# WiirdFlex_Bottom_Alignment.net
KiCad netlist of a schematic drawn in Altium Designer
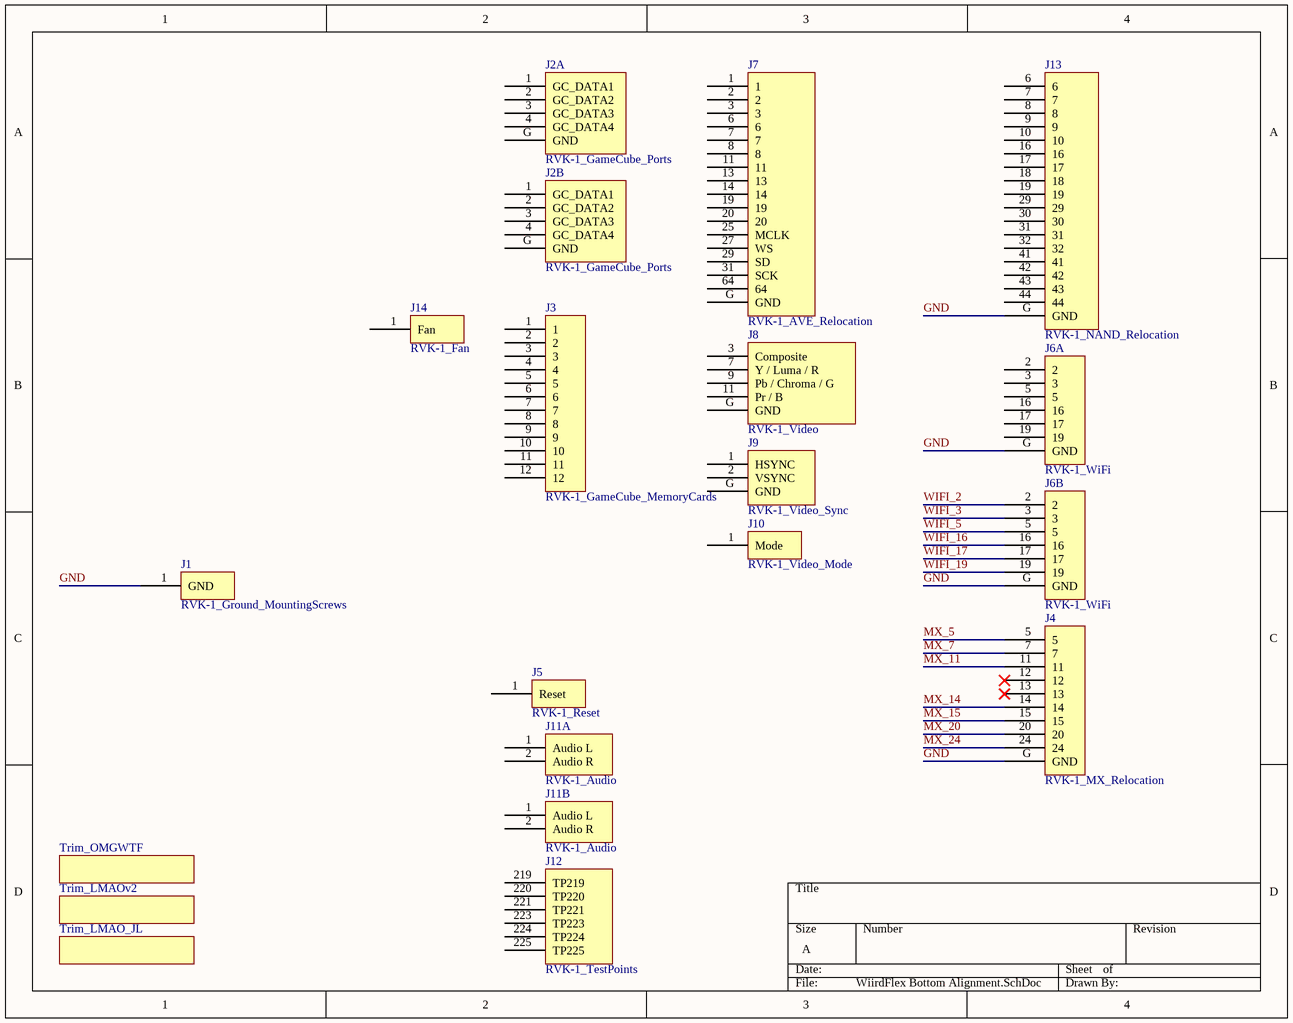
[diagram p0: WiirdFlex Bottom Alignment.SchDoc]

(export (version "E")
  (design (tool "Eeschema 10.0.6"))
  (components
    (comp (ref "J1")
      (value "RVK-1_Ground_MountingScrews")
      (footprint "RVK-1_GND_Screws - bottom alignment board")
      (libsource (lib "WiirdFlex") (part "RVK-1_Ground_MountingScrews"))
    )
    (comp (ref "J2A")
      (value "RVK-1_GameCube_Ports")
      (footprint "RVK-1_GC_Controller_RPads - alignment")
      (libsource (lib "WiirdFlex") (part "RVK-1_GameCube_Ports"))
    )
    (comp (ref "J2B")
      (value "RVK-1_GameCube_Ports")
      (footprint "RVK-1_GC_Controller_Vias - alignment")
      (libsource (lib "WiirdFlex") (part "RVK-1_GameCube_Ports"))
    )
    (comp (ref "J3")
      (value "RVK-1_GameCube_MemoryCards")
      (footprint "RVK-1_MemCard_TestPoints - alignment")
      (libsource (lib "WiirdFlex") (part "RVK-1_GameCube_MemoryCards"))
    )
    (comp (ref "J4")
      (value "RVK-1_MX_Relocation")
      (footprint "RVK-1_MX - alignment")
      (libsource (lib "WiirdFlex") (part "RVK-1_MX_Relocation"))
    )
    (comp (ref "J5")
      (value "RVK-1_Reset")
      (footprint "RVK-1_Reset - alignment")
      (libsource (lib "WiirdFlex") (part "RVK-1_Reset"))
    )
    (comp (ref "J6A")
      (value "RVK-1_WiFi")
      (footprint "RVK-1_WiFi_RPads - Alignment")
      (libsource (lib "WiirdFlex") (part "RVK-1_WiFi"))
    )
    (comp (ref "J6B")
      (value "RVK-1_WiFi")
      (footprint "RVK-1_WiFi_Vias - Alignment")
      (libsource (lib "WiirdFlex") (part "RVK-1_WiFi"))
    )
    (comp (ref "J7")
      (value "RVK-1_AVE_Relocation")
      (footprint "RVK-1_AVE_Vias - alignment")
      (libsource (lib "WiirdFlex") (part "RVK-1_AVE_Relocation"))
    )
    (comp (ref "J8")
      (value "RVK-1_Video")
      (footprint "RVK-1_Video_Vias - alignment")
      (libsource (lib "WiirdFlex") (part "RVK-1_Video"))
    )
    (comp (ref "J9")
      (value "RVK-1_Video_Sync")
      (footprint "RVK-1_Video_Sync - alignment")
      (libsource (lib "WiirdFlex") (part "RVK-1_Video_Sync"))
    )
    (comp (ref "J10")
      (value "RVK-1_Video_Mode")
      (footprint "RVK-1_Video_Mode_via - alignment")
      (libsource (lib "WiirdFlex") (part "RVK-1_Video_Mode"))
    )
    (comp (ref "J11A")
      (value "RVK-1_Audio")
      (footprint "RVK-1_AVE_Audio_Out - alignment")
      (libsource (lib "WiirdFlex") (part "RVK-1_Audio"))
    )
    (comp (ref "J11B")
      (value "RVK-1_Audio")
      (footprint "RVK-1_Audio_Preamp_Pads - alignment")
      (libsource (lib "WiirdFlex") (part "RVK-1_Audio"))
    )
    (comp (ref "J12")
      (value "RVK-1_TestPoints")
      (footprint "RVK-1_TestPoint_Vias - alignment")
      (libsource (lib "WiirdFlex") (part "RVK-1_TestPoints"))
    )
    (comp (ref "J13")
      (value "RVK-1_NAND_Relocation")
      (footprint "RVK-1_NAND_Vias - alignment")
      (libsource (lib "WiirdFlex") (part "RVK-1_NAND_Relocation"))
    )
    (comp (ref "J14")
      (value "RVK-1_Fan")
      (footprint "RVK-1_Fan_PWM - alignment")
      (libsource (lib "WiirdFlex") (part "RVK-1_Fan"))
    )
    (comp (ref "Trim_LMAOv2")
      (value "Misc")
      (footprint "Wii trim: LMAOv2")
      (description "placeholder for footprints without pads - keepouts, trim outlines, etc")
      (libsource (lib "WiirdFlex") (part "Misc"))
    )
    (comp (ref "Trim_LMAO_JL")
      (value "Misc")
      (footprint "Wii Trim: LMAO with extra mounting hole")
      (description "placeholder for footprints without pads - keepouts, trim outlines, etc")
      (libsource (lib "WiirdFlex") (part "Misc"))
    )
    (comp (ref "Trim_OMGWTF")
      (value "Misc")
      (footprint "Wii trim: OMGWTF")
      (description "placeholder for footprints without pads - keepouts, trim outlines, etc")
      (libsource (lib "WiirdFlex") (part "Misc"))
    )
  )
  (nets
    (net (code "1") (name "/GND") (class "Default")
      (node (ref "J1") (pin "1") (pinfunction "GND_1") (pintype "passive"))
      (node (ref "J13") (pin "G") (pinfunction "GND_G") (pintype "passive"))
      (node (ref "J4") (pin "G") (pinfunction "GND_G") (pintype "passive"))
      (node (ref "J6A") (pin "G") (pinfunction "GND_G") (pintype "passive"))
      (node (ref "J6B") (pin "G") (pinfunction "GND_G") (pintype "passive"))
    )
    (net (code "2") (name "/MX_5") (class "Default")
      (node (ref "J4") (pin "5") (pinfunction "5_5") (pintype "passive"))
    )
    (net (code "3") (name "/MX_7") (class "Default")
      (node (ref "J4") (pin "7") (pinfunction "7_7") (pintype "passive"))
    )
    (net (code "4") (name "/MX_11") (class "Default")
      (node (ref "J4") (pin "11") (pinfunction "11_11") (pintype "passive"))
    )
    (net (code "5") (name "/MX_14") (class "Default")
      (node (ref "J4") (pin "14") (pinfunction "14_14") (pintype "passive"))
    )
    (net (code "6") (name "/MX_15") (class "Default")
      (node (ref "J4") (pin "15") (pinfunction "15_15") (pintype "passive"))
    )
    (net (code "7") (name "/MX_20") (class "Default")
      (node (ref "J4") (pin "20") (pinfunction "20_20") (pintype "passive"))
    )
    (net (code "8") (name "/MX_24") (class "Default")
      (node (ref "J4") (pin "24") (pinfunction "24_24") (pintype "passive"))
    )
    (net (code "9") (name "/WIFI_2") (class "Default")
      (node (ref "J6B") (pin "2") (pinfunction "2_2") (pintype "passive"))
    )
    (net (code "10") (name "/WIFI_3") (class "Default")
      (node (ref "J6B") (pin "3") (pinfunction "3_3") (pintype "passive"))
    )
    (net (code "11") (name "/WIFI_5") (class "Default")
      (node (ref "J6B") (pin "5") (pinfunction "5_5") (pintype "passive"))
    )
    (net (code "12") (name "/WIFI_16") (class "Default")
      (node (ref "J6B") (pin "16") (pinfunction "16_16") (pintype "passive"))
    )
    (net (code "13") (name "/WIFI_17") (class "Default")
      (node (ref "J6B") (pin "17") (pinfunction "17_17") (pintype "passive"))
    )
    (net (code "14") (name "/WIFI_19") (class "Default")
      (node (ref "J6B") (pin "19") (pinfunction "19_19") (pintype "passive"))
    )
    (net (code "15") (name "unconnected-(J2A-GC_DATA1-Pad1)") (class "Default")
      (node (ref "J2A") (pin "1") (pinfunction "GC_DATA1_1") (pintype "passive"))
    )
    (net (code "16") (name "unconnected-(J2A-GC_DATA2-Pad2)") (class "Default")
      (node (ref "J2A") (pin "2") (pinfunction "GC_DATA2_2") (pintype "passive"))
    )
    (net (code "17") (name "unconnected-(J2A-GC_DATA3-Pad3)") (class "Default")
      (node (ref "J2A") (pin "3") (pinfunction "GC_DATA3_3") (pintype "passive"))
    )
    (net (code "18") (name "unconnected-(J2A-GC_DATA4-Pad4)") (class "Default")
      (node (ref "J2A") (pin "4") (pinfunction "GC_DATA4_4") (pintype "passive"))
    )
    (net (code "19") (name "unconnected-(J2A-GND-PadG)") (class "Default")
      (node (ref "J2A") (pin "G") (pinfunction "GND_G") (pintype "passive"))
    )
    (net (code "20") (name "unconnected-(J2B-GC_DATA1-Pad1)") (class "Default")
      (node (ref "J2B") (pin "1") (pinfunction "GC_DATA1_1") (pintype "passive"))
    )
    (net (code "21") (name "unconnected-(J2B-GC_DATA2-Pad2)") (class "Default")
      (node (ref "J2B") (pin "2") (pinfunction "GC_DATA2_2") (pintype "passive"))
    )
    (net (code "22") (name "unconnected-(J2B-GC_DATA3-Pad3)") (class "Default")
      (node (ref "J2B") (pin "3") (pinfunction "GC_DATA3_3") (pintype "passive"))
    )
    (net (code "23") (name "unconnected-(J2B-GC_DATA4-Pad4)") (class "Default")
      (node (ref "J2B") (pin "4") (pinfunction "GC_DATA4_4") (pintype "passive"))
    )
    (net (code "24") (name "unconnected-(J2B-GND-PadG)") (class "Default")
      (node (ref "J2B") (pin "G") (pinfunction "GND_G") (pintype "passive"))
    )
    (net (code "25") (name "unconnected-(J3-Pad1)") (class "Default")
      (node (ref "J3") (pin "1") (pinfunction "1_1") (pintype "passive"))
    )
    (net (code "26") (name "unconnected-(J3-Pad2)") (class "Default")
      (node (ref "J3") (pin "2") (pinfunction "2_2") (pintype "passive"))
    )
    (net (code "27") (name "unconnected-(J3-Pad3)") (class "Default")
      (node (ref "J3") (pin "3") (pinfunction "3_3") (pintype "passive"))
    )
    (net (code "28") (name "unconnected-(J3-Pad4)") (class "Default")
      (node (ref "J3") (pin "4") (pinfunction "4_4") (pintype "passive"))
    )
    (net (code "29") (name "unconnected-(J3-Pad5)") (class "Default")
      (node (ref "J3") (pin "5") (pinfunction "5_5") (pintype "passive"))
    )
    (net (code "30") (name "unconnected-(J3-Pad6)") (class "Default")
      (node (ref "J3") (pin "6") (pinfunction "6_6") (pintype "passive"))
    )
    (net (code "31") (name "unconnected-(J3-Pad7)") (class "Default")
      (node (ref "J3") (pin "7") (pinfunction "7_7") (pintype "passive"))
    )
    (net (code "32") (name "unconnected-(J3-Pad8)") (class "Default")
      (node (ref "J3") (pin "8") (pinfunction "8_8") (pintype "passive"))
    )
    (net (code "33") (name "unconnected-(J3-Pad9)") (class "Default")
      (node (ref "J3") (pin "9") (pinfunction "9_9") (pintype "passive"))
    )
    (net (code "34") (name "unconnected-(J3-Pad10)") (class "Default")
      (node (ref "J3") (pin "10") (pinfunction "10_10") (pintype "passive"))
    )
    (net (code "35") (name "unconnected-(J3-Pad11)") (class "Default")
      (node (ref "J3") (pin "11") (pinfunction "11_11") (pintype "passive"))
    )
    (net (code "36") (name "unconnected-(J3-Pad12)") (class "Default")
      (node (ref "J3") (pin "12") (pinfunction "12_12") (pintype "passive"))
    )
    (net (code "37") (name "unconnected-(J4-Pad12)") (class "Default")
      (node (ref "J4") (pin "12") (pinfunction "12_12") (pintype "passive+no_connect"))
    )
    (net (code "38") (name "unconnected-(J4-Pad13)") (class "Default")
      (node (ref "J4") (pin "13") (pinfunction "13_13") (pintype "passive+no_connect"))
    )
    (net (code "39") (name "unconnected-(J5-Reset-Pad1)") (class "Default")
      (node (ref "J5") (pin "1") (pinfunction "Reset_1") (pintype "passive"))
    )
    (net (code "40") (name "unconnected-(J6A-Pad2)") (class "Default")
      (node (ref "J6A") (pin "2") (pinfunction "2_2") (pintype "passive"))
    )
    (net (code "41") (name "unconnected-(J6A-Pad3)") (class "Default")
      (node (ref "J6A") (pin "3") (pinfunction "3_3") (pintype "passive"))
    )
    (net (code "42") (name "unconnected-(J6A-Pad5)") (class "Default")
      (node (ref "J6A") (pin "5") (pinfunction "5_5") (pintype "passive"))
    )
    (net (code "43") (name "unconnected-(J6A-Pad16)") (class "Default")
      (node (ref "J6A") (pin "16") (pinfunction "16_16") (pintype "passive"))
    )
    (net (code "44") (name "unconnected-(J6A-Pad17)") (class "Default")
      (node (ref "J6A") (pin "17") (pinfunction "17_17") (pintype "passive"))
    )
    (net (code "45") (name "unconnected-(J6A-Pad19)") (class "Default")
      (node (ref "J6A") (pin "19") (pinfunction "19_19") (pintype "passive"))
    )
    (net (code "46") (name "unconnected-(J7-GND-PadG)") (class "Default")
      (node (ref "J7") (pin "G") (pinfunction "GND_G") (pintype "passive"))
    )
    (net (code "47") (name "unconnected-(J7-MCLK-Pad25)") (class "Default")
      (node (ref "J7") (pin "25") (pinfunction "MCLK_25") (pintype "passive"))
    )
    (net (code "48") (name "unconnected-(J7-Pad1)") (class "Default")
      (node (ref "J7") (pin "1") (pinfunction "1_1") (pintype "passive"))
    )
    (net (code "49") (name "unconnected-(J7-Pad2)") (class "Default")
      (node (ref "J7") (pin "2") (pinfunction "2_2") (pintype "passive"))
    )
    (net (code "50") (name "unconnected-(J7-Pad3)") (class "Default")
      (node (ref "J7") (pin "3") (pinfunction "3_3") (pintype "passive"))
    )
    (net (code "51") (name "unconnected-(J7-Pad6)") (class "Default")
      (node (ref "J7") (pin "6") (pinfunction "6_6") (pintype "passive"))
    )
    (net (code "52") (name "unconnected-(J7-Pad7)") (class "Default")
      (node (ref "J7") (pin "7") (pinfunction "7_7") (pintype "passive"))
    )
    (net (code "53") (name "unconnected-(J7-Pad8)") (class "Default")
      (node (ref "J7") (pin "8") (pinfunction "8_8") (pintype "passive"))
    )
    (net (code "54") (name "unconnected-(J7-Pad11)") (class "Default")
      (node (ref "J7") (pin "11") (pinfunction "11_11") (pintype "passive"))
    )
    (net (code "55") (name "unconnected-(J7-Pad13)") (class "Default")
      (node (ref "J7") (pin "13") (pinfunction "13_13") (pintype "passive"))
    )
    (net (code "56") (name "unconnected-(J7-Pad14)") (class "Default")
      (node (ref "J7") (pin "14") (pinfunction "14_14") (pintype "passive"))
    )
    (net (code "57") (name "unconnected-(J7-Pad19)") (class "Default")
      (node (ref "J7") (pin "19") (pinfunction "19_19") (pintype "passive"))
    )
    (net (code "58") (name "unconnected-(J7-Pad20)") (class "Default")
      (node (ref "J7") (pin "20") (pinfunction "20_20") (pintype "passive"))
    )
    (net (code "59") (name "unconnected-(J7-Pad64)") (class "Default")
      (node (ref "J7") (pin "64") (pinfunction "64_64") (pintype "passive"))
    )
    (net (code "60") (name "unconnected-(J7-SCK-Pad31)") (class "Default")
      (node (ref "J7") (pin "31") (pinfunction "SCK_31") (pintype "passive"))
    )
    (net (code "61") (name "unconnected-(J7-SD-Pad29)") (class "Default")
      (node (ref "J7") (pin "29") (pinfunction "SD_29") (pintype "passive"))
    )
    (net (code "62") (name "unconnected-(J7-WS-Pad27)") (class "Default")
      (node (ref "J7") (pin "27") (pinfunction "WS_27") (pintype "passive"))
    )
    (net (code "63") (name "unconnected-(J8-Composite-Pad3)") (class "Default")
      (node (ref "J8") (pin "3") (pinfunction "Composite_3") (pintype "passive"))
    )
    (net (code "64") (name "unconnected-(J8-GND-PadG)") (class "Default")
      (node (ref "J8") (pin "G") (pinfunction "GND_G") (pintype "passive"))
    )
    (net (code "65") (name "unconnected-(J8-Pb_{slash}_Chroma_{slash}_G-Pad9)") (class "Default")
      (node (ref "J8") (pin "9") (pinfunction "Pb_/_Chroma_/_G_9") (pintype "passive"))
    )
    (net (code "66") (name "unconnected-(J8-Pr_{slash}_B-Pad11)") (class "Default")
      (node (ref "J8") (pin "11") (pinfunction "Pr_/_B_11") (pintype "passive"))
    )
    (net (code "67") (name "unconnected-(J8-Y_{slash}_Luma_{slash}_R-Pad7)") (class "Default")
      (node (ref "J8") (pin "7") (pinfunction "Y_/_Luma_/_R_7") (pintype "passive"))
    )
    (net (code "68") (name "unconnected-(J9-GND-PadG)") (class "Default")
      (node (ref "J9") (pin "G") (pinfunction "GND_G") (pintype "passive"))
    )
    (net (code "69") (name "unconnected-(J9-HSYNC-Pad1)") (class "Default")
      (node (ref "J9") (pin "1") (pinfunction "HSYNC_1") (pintype "passive"))
    )
    (net (code "70") (name "unconnected-(J9-VSYNC-Pad2)") (class "Default")
      (node (ref "J9") (pin "2") (pinfunction "VSYNC_2") (pintype "passive"))
    )
    (net (code "71") (name "unconnected-(J10-Mode-Pad1)") (class "Default")
      (node (ref "J10") (pin "1") (pinfunction "Mode_1") (pintype "passive"))
    )
    (net (code "72") (name "unconnected-(J11A-Audio_L-Pad1)") (class "Default")
      (node (ref "J11A") (pin "1") (pinfunction "Audio_L_1") (pintype "passive"))
    )
    (net (code "73") (name "unconnected-(J11A-Audio_R-Pad2)") (class "Default")
      (node (ref "J11A") (pin "2") (pinfunction "Audio_R_2") (pintype "passive"))
    )
    (net (code "74") (name "unconnected-(J11B-Audio_L-Pad1)") (class "Default")
      (node (ref "J11B") (pin "1") (pinfunction "Audio_L_1") (pintype "passive"))
    )
    (net (code "75") (name "unconnected-(J11B-Audio_R-Pad2)") (class "Default")
      (node (ref "J11B") (pin "2") (pinfunction "Audio_R_2") (pintype "passive"))
    )
    (net (code "76") (name "unconnected-(J12-TP219-Pad219)") (class "Default")
      (node (ref "J12") (pin "219") (pinfunction "TP219_219") (pintype "passive"))
    )
    (net (code "77") (name "unconnected-(J12-TP220-Pad220)") (class "Default")
      (node (ref "J12") (pin "220") (pinfunction "TP220_220") (pintype "passive"))
    )
    (net (code "78") (name "unconnected-(J12-TP221-Pad221)") (class "Default")
      (node (ref "J12") (pin "221") (pinfunction "TP221_221") (pintype "passive"))
    )
    (net (code "79") (name "unconnected-(J12-TP223-Pad223)") (class "Default")
      (node (ref "J12") (pin "223") (pinfunction "TP223_223") (pintype "passive"))
    )
    (net (code "80") (name "unconnected-(J12-TP224-Pad224)") (class "Default")
      (node (ref "J12") (pin "224") (pinfunction "TP224_224") (pintype "passive"))
    )
    (net (code "81") (name "unconnected-(J12-TP225-Pad225)") (class "Default")
      (node (ref "J12") (pin "225") (pinfunction "TP225_225") (pintype "passive"))
    )
    (net (code "82") (name "unconnected-(J13-Pad6)") (class "Default")
      (node (ref "J13") (pin "6") (pinfunction "6_6") (pintype "passive"))
    )
    (net (code "83") (name "unconnected-(J13-Pad7)") (class "Default")
      (node (ref "J13") (pin "7") (pinfunction "7_7") (pintype "passive"))
    )
    (net (code "84") (name "unconnected-(J13-Pad8)") (class "Default")
      (node (ref "J13") (pin "8") (pinfunction "8_8") (pintype "passive"))
    )
    (net (code "85") (name "unconnected-(J13-Pad9)") (class "Default")
      (node (ref "J13") (pin "9") (pinfunction "9_9") (pintype "passive"))
    )
    (net (code "86") (name "unconnected-(J13-Pad10)") (class "Default")
      (node (ref "J13") (pin "10") (pinfunction "10_10") (pintype "passive"))
    )
    (net (code "87") (name "unconnected-(J13-Pad16)") (class "Default")
      (node (ref "J13") (pin "16") (pinfunction "16_16") (pintype "passive"))
    )
    (net (code "88") (name "unconnected-(J13-Pad17)") (class "Default")
      (node (ref "J13") (pin "17") (pinfunction "17_17") (pintype "passive"))
    )
    (net (code "89") (name "unconnected-(J13-Pad18)") (class "Default")
      (node (ref "J13") (pin "18") (pinfunction "18_18") (pintype "passive"))
    )
    (net (code "90") (name "unconnected-(J13-Pad19)") (class "Default")
      (node (ref "J13") (pin "19") (pinfunction "19_19") (pintype "passive"))
    )
    (net (code "91") (name "unconnected-(J13-Pad29)") (class "Default")
      (node (ref "J13") (pin "29") (pinfunction "29_29") (pintype "passive"))
    )
    (net (code "92") (name "unconnected-(J13-Pad30)") (class "Default")
      (node (ref "J13") (pin "30") (pinfunction "30_30") (pintype "passive"))
    )
    (net (code "93") (name "unconnected-(J13-Pad31)") (class "Default")
      (node (ref "J13") (pin "31") (pinfunction "31_31") (pintype "passive"))
    )
    (net (code "94") (name "unconnected-(J13-Pad32)") (class "Default")
      (node (ref "J13") (pin "32") (pinfunction "32_32") (pintype "passive"))
    )
    (net (code "95") (name "unconnected-(J13-Pad41)") (class "Default")
      (node (ref "J13") (pin "41") (pinfunction "41_41") (pintype "passive"))
    )
    (net (code "96") (name "unconnected-(J13-Pad42)") (class "Default")
      (node (ref "J13") (pin "42") (pinfunction "42_42") (pintype "passive"))
    )
    (net (code "97") (name "unconnected-(J13-Pad43)") (class "Default")
      (node (ref "J13") (pin "43") (pinfunction "43_43") (pintype "passive"))
    )
    (net (code "98") (name "unconnected-(J13-Pad44)") (class "Default")
      (node (ref "J13") (pin "44") (pinfunction "44_44") (pintype "passive"))
    )
    (net (code "99") (name "unconnected-(J14-Fan-Pad1)") (class "Default")
      (node (ref "J14") (pin "1") (pinfunction "Fan_1") (pintype "passive"))
    )
  )
)
